# screen.net
KiCad netlist of a schematic drawn in Altium Designer
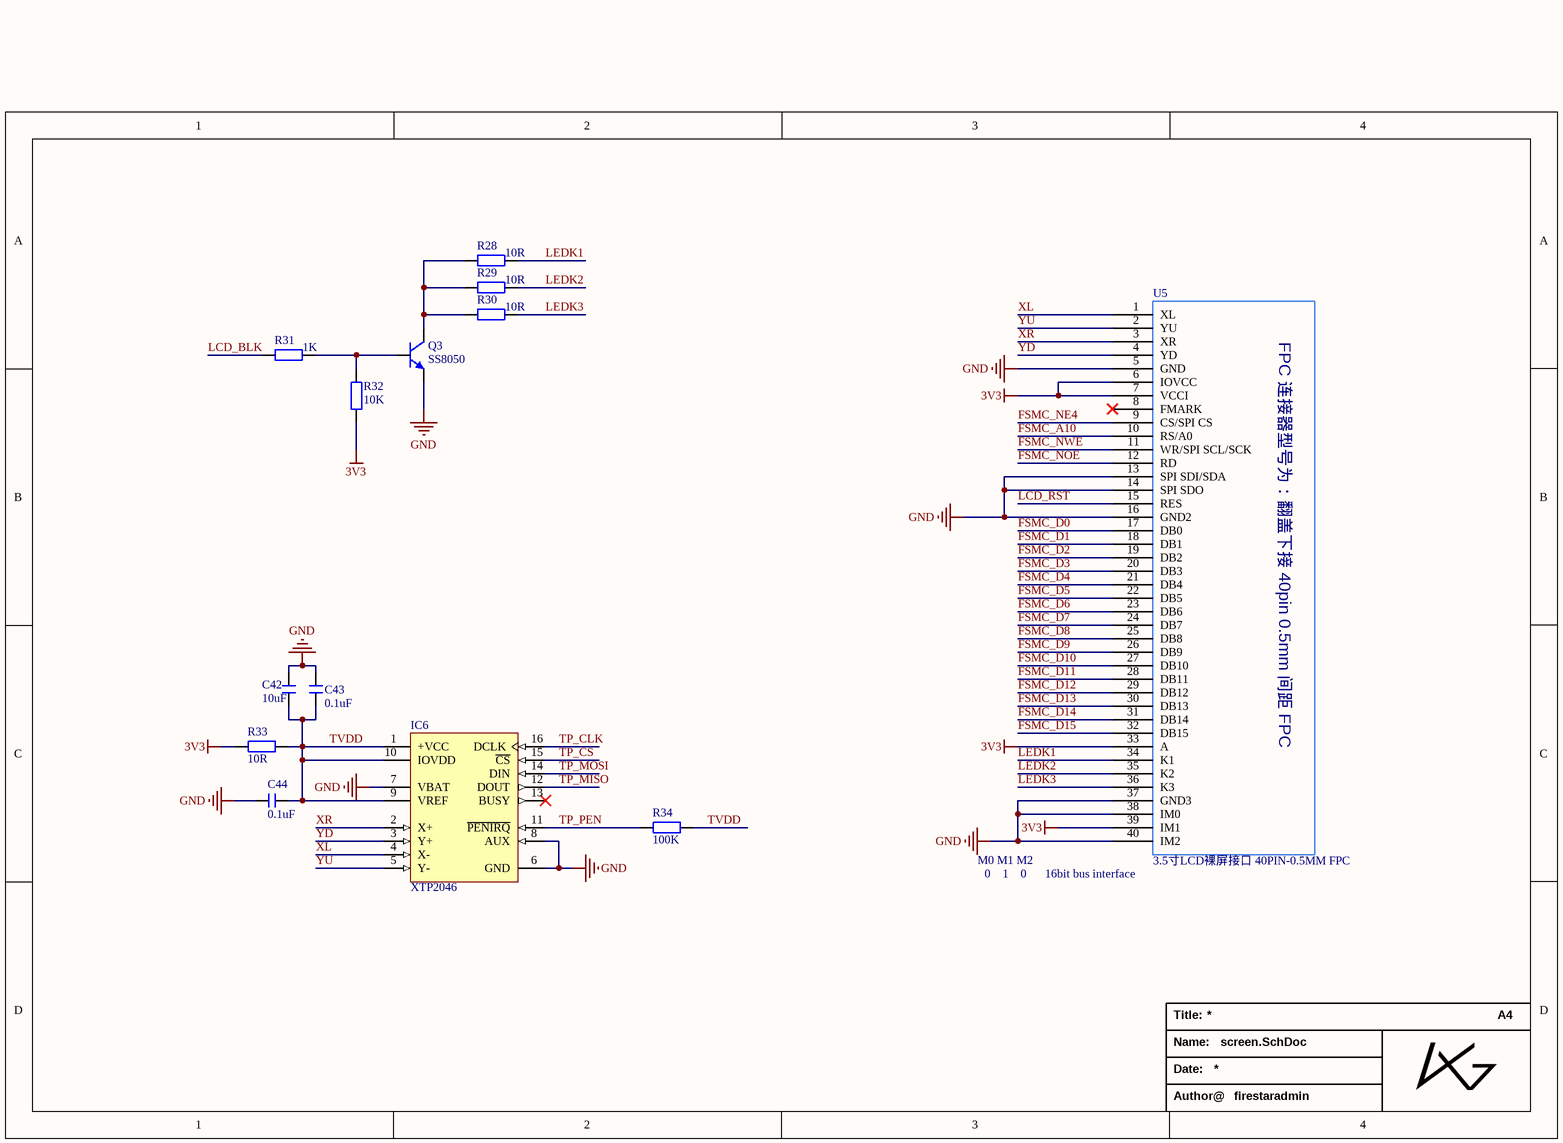
[diagram p0: screen.SchDoc]

(export (version "E")
  (design (tool "Eeschema 10.0.6"))
  (components
    (comp (ref "C42")
      (value "10uF")
      (footprint "C 0603_M")
      (description "无极性贴片电容")
      (fields (field (name "版权归属") "源创客"))
      (libsource (lib "3.1   - 电阻-电容-电感") (part "C"))
    )
    (comp (ref "C43")
      (value "0.1uF")
      (footprint "C 0603_M")
      (description "无极性贴片电容")
      (fields (field (name "版权归属") "源创客"))
      (libsource (lib "3.1   - 电阻-电容-电感") (part "C"))
    )
    (comp (ref "C44")
      (value "0.1uF")
      (footprint "C 0603_M")
      (description "无极性贴片电容")
      (fields (field (name "版权归属") "源创客"))
      (libsource (lib "3.1   - 电阻-电容-电感") (part "C"))
    )
    (comp (ref "IC6")
      (value "XTP2046")
      (footprint "TSSOP16_M")
      (description "显示屏触摸驱动芯片")
      (fields (field (name "版权归属") "源创客"))
      (libsource (lib "1.1   - IC芯片") (part "TSC2046IPW"))
    )
    (comp (ref "Q3")
      (value "SS8050")
      (footprint "SOT23-3M")
      (description "高频放大-NPN型")
      (fields (field (name "版权归属") "源创客"))
      (libsource (lib "6.2   - 三极管") (part "8050-SMD"))
    )
    (comp (ref "R28")
      (value "10R")
      (footprint "R 0603_M")
      (description "贴片电阻")
      (fields (field (name "版权归属") "源创客"))
      (libsource (lib "3.1   - 电阻-电容-电感") (part "R"))
    )
    (comp (ref "R29")
      (value "10R")
      (footprint "R 0603_M")
      (description "贴片电阻")
      (fields (field (name "版权归属") "源创客"))
      (libsource (lib "3.1   - 电阻-电容-电感") (part "R"))
    )
    (comp (ref "R30")
      (value "10R")
      (footprint "R 0603_M")
      (description "贴片电阻")
      (fields (field (name "版权归属") "源创客"))
      (libsource (lib "3.1   - 电阻-电容-电感") (part "R"))
    )
    (comp (ref "R31")
      (value "1K")
      (footprint "R 0603_M")
      (description "贴片电阻")
      (fields (field (name "版权归属") "源创客"))
      (libsource (lib "3.1   - 电阻-电容-电感") (part "R"))
    )
    (comp (ref "R32")
      (value "10K")
      (footprint "R 0603_M")
      (description "贴片电阻")
      (fields (field (name "版权归属") "源创客"))
      (libsource (lib "3.1   - 电阻-电容-电感") (part "R"))
    )
    (comp (ref "R33")
      (value "10R")
      (footprint "R 0603_M")
      (description "贴片电阻")
      (fields (field (name "版权归属") "源创客"))
      (libsource (lib "3.1   - 电阻-电容-电感") (part "R"))
    )
    (comp (ref "R34")
      (value "100K")
      (footprint "R 0603_M")
      (description "贴片电阻")
      (fields (field (name "版权归属") "源创客"))
      (libsource (lib "3.1   - 电阻-电容-电感") (part "R"))
    )
    (comp (ref "U5")
      (value "3.5寸LCD裸屏接口 40PIN-0.5MM FPC")
      (footprint "FPC0.5 2H-WS-40P")
      (description "3.5寸LCD屏幕 40PIN-0.5MM FPC 接口")
      (libsource (lib "MyLib") (part "3.5寸LCD裸屏接口 40PIN-0.5MM FPC"))
    )
  )
  (nets
    (net (code "1") (name "/FSMC_A10") (class "Default")
      (node (ref "U5") (pin "10") (pinfunction "RS/A0_10") (pintype "passive"))
    )
    (net (code "2") (name "/FSMC_D0") (class "Default")
      (node (ref "U5") (pin "17") (pinfunction "DB0_17") (pintype "passive"))
    )
    (net (code "3") (name "/FSMC_D1") (class "Default")
      (node (ref "U5") (pin "18") (pinfunction "DB1_18") (pintype "passive"))
    )
    (net (code "4") (name "/FSMC_D2") (class "Default")
      (node (ref "U5") (pin "19") (pinfunction "DB2_19") (pintype "passive"))
    )
    (net (code "5") (name "/FSMC_D3") (class "Default")
      (node (ref "U5") (pin "20") (pinfunction "DB3_20") (pintype "passive"))
    )
    (net (code "6") (name "/FSMC_D4") (class "Default")
      (node (ref "U5") (pin "21") (pinfunction "DB4_21") (pintype "passive"))
    )
    (net (code "7") (name "/FSMC_D5") (class "Default")
      (node (ref "U5") (pin "22") (pinfunction "DB5_22") (pintype "passive"))
    )
    (net (code "8") (name "/FSMC_D6") (class "Default")
      (node (ref "U5") (pin "23") (pinfunction "DB6_23") (pintype "passive"))
    )
    (net (code "9") (name "/FSMC_D7") (class "Default")
      (node (ref "U5") (pin "24") (pinfunction "DB7_24") (pintype "passive"))
    )
    (net (code "10") (name "/FSMC_D8") (class "Default")
      (node (ref "U5") (pin "25") (pinfunction "DB8_25") (pintype "passive"))
    )
    (net (code "11") (name "/FSMC_D9") (class "Default")
      (node (ref "U5") (pin "26") (pinfunction "DB9_26") (pintype "passive"))
    )
    (net (code "12") (name "/FSMC_D10") (class "Default")
      (node (ref "U5") (pin "27") (pinfunction "DB10_27") (pintype "passive"))
    )
    (net (code "13") (name "/FSMC_D11") (class "Default")
      (node (ref "U5") (pin "28") (pinfunction "DB11_28") (pintype "passive"))
    )
    (net (code "14") (name "/FSMC_D12") (class "Default")
      (node (ref "U5") (pin "29") (pinfunction "DB12_29") (pintype "passive"))
    )
    (net (code "15") (name "/FSMC_D13") (class "Default")
      (node (ref "U5") (pin "30") (pinfunction "DB13_30") (pintype "passive"))
    )
    (net (code "16") (name "/FSMC_D14") (class "Default")
      (node (ref "U5") (pin "31") (pinfunction "DB14_31") (pintype "passive"))
    )
    (net (code "17") (name "/FSMC_D15") (class "Default")
      (node (ref "U5") (pin "32") (pinfunction "DB15_32") (pintype "passive"))
    )
    (net (code "18") (name "/FSMC_NE4") (class "Default")
      (node (ref "U5") (pin "9") (pinfunction "CS/SPI_CS_9") (pintype "passive"))
    )
    (net (code "19") (name "/FSMC_NOE") (class "Default")
      (node (ref "U5") (pin "12") (pinfunction "RD_12") (pintype "passive"))
    )
    (net (code "20") (name "/FSMC_NWE") (class "Default")
      (node (ref "U5") (pin "11") (pinfunction "WR/SPI_SCL/SCK_11") (pintype "passive"))
    )
    (net (code "21") (name "/LCD_BLK") (class "Default")
      (node (ref "R31") (pin "1") (pinfunction "1_1") (pintype "passive"))
    )
    (net (code "22") (name "/LCD_RST") (class "Default")
      (node (ref "U5") (pin "15") (pinfunction "RES_15") (pintype "passive"))
    )
    (net (code "23") (name "/LEDK1") (class "Default")
      (node (ref "R28") (pin "2") (pinfunction "2_2") (pintype "passive"))
      (node (ref "U5") (pin "34") (pinfunction "K1_34") (pintype "passive"))
    )
    (net (code "24") (name "/LEDK2") (class "Default")
      (node (ref "R29") (pin "2") (pinfunction "2_2") (pintype "passive"))
      (node (ref "U5") (pin "35") (pinfunction "K2_35") (pintype "passive"))
    )
    (net (code "25") (name "/LEDK3") (class "Default")
      (node (ref "R30") (pin "2") (pinfunction "2_2") (pintype "passive"))
      (node (ref "U5") (pin "36") (pinfunction "K3_36") (pintype "passive"))
    )
    (net (code "26") (name "/TP_CLK") (class "Default")
      (node (ref "IC6") (pin "16") (pinfunction "DCLK_16") (pintype "input"))
    )
    (net (code "27") (name "/TP_CS") (class "Default")
      (node (ref "IC6") (pin "15") (pinfunction "~{CS}_15") (pintype "input"))
    )
    (net (code "28") (name "/TP_MISO") (class "Default")
      (node (ref "IC6") (pin "12") (pinfunction "DOUT_12") (pintype "output"))
    )
    (net (code "29") (name "/TP_MOSI") (class "Default")
      (node (ref "IC6") (pin "14") (pinfunction "DIN_14") (pintype "input"))
    )
    (net (code "30") (name "/TP_PEN") (class "Default")
      (node (ref "IC6") (pin "11") (pinfunction "~{PENIRQ}_11") (pintype "input"))
      (node (ref "R34") (pin "1") (pinfunction "1_1") (pintype "passive"))
    )
    (net (code "31") (name "/TVDD") (class "Default")
      (node (ref "C42") (pin "2") (pinfunction "2_2") (pintype "passive"))
      (node (ref "C43") (pin "2") (pinfunction "2_2") (pintype "passive"))
      (node (ref "C44") (pin "1") (pinfunction "1_1") (pintype "passive"))
      (node (ref "IC6") (pin "1") (pinfunction "+VCC_1") (pintype "power_in"))
      (node (ref "IC6") (pin "10") (pinfunction "IOVDD_10") (pintype "power_in"))
      (node (ref "IC6") (pin "9") (pinfunction "VREF_9") (pintype "power_in"))
      (node (ref "R33") (pin "2") (pinfunction "2_2") (pintype "passive"))
      (node (ref "R34") (pin "2") (pinfunction "2_2") (pintype "passive"))
    )
    (net (code "32") (name "/XL") (class "Default")
      (node (ref "IC6") (pin "4") (pinfunction "X-_4") (pintype "input"))
      (node (ref "U5") (pin "1") (pinfunction "XL_1") (pintype "passive"))
    )
    (net (code "33") (name "/XR") (class "Default")
      (node (ref "IC6") (pin "2") (pinfunction "X+_2") (pintype "input"))
      (node (ref "U5") (pin "3") (pinfunction "XR_3") (pintype "passive"))
    )
    (net (code "34") (name "/YD") (class "Default")
      (node (ref "IC6") (pin "3") (pinfunction "Y+_3") (pintype "input"))
      (node (ref "U5") (pin "4") (pinfunction "YD_4") (pintype "passive"))
    )
    (net (code "35") (name "/YU") (class "Default")
      (node (ref "IC6") (pin "5") (pinfunction "Y-_5") (pintype "input"))
      (node (ref "U5") (pin "2") (pinfunction "YU_2") (pintype "passive"))
    )
    (net (code "36") (name "3V3") (class "Default")
      (node (ref "R32") (pin "1") (pinfunction "1_1") (pintype "passive"))
      (node (ref "R33") (pin "1") (pinfunction "1_1") (pintype "passive"))
      (node (ref "U5") (pin "33") (pinfunction "A_33") (pintype "passive"))
      (node (ref "U5") (pin "39") (pinfunction "IM1_39") (pintype "passive"))
      (node (ref "U5") (pin "6") (pinfunction "IOVCC_6") (pintype "passive"))
      (node (ref "U5") (pin "7") (pinfunction "VCCI_7") (pintype "passive"))
    )
    (net (code "37") (name "GND") (class "Default")
      (node (ref "C42") (pin "1") (pinfunction "1_1") (pintype "passive"))
      (node (ref "C43") (pin "1") (pinfunction "1_1") (pintype "passive"))
      (node (ref "C44") (pin "2") (pinfunction "2_2") (pintype "passive"))
      (node (ref "IC6") (pin "6") (pinfunction "GND_6") (pintype "power_in"))
      (node (ref "IC6") (pin "7") (pinfunction "VBAT_7") (pintype "power_in"))
      (node (ref "IC6") (pin "8") (pinfunction "AUX_8") (pintype "input"))
      (node (ref "Q3") (pin "2") (pinfunction "E_2") (pintype "passive"))
      (node (ref "U5") (pin "13") (pinfunction "SPI_SDI/SDA_13") (pintype "passive"))
      (node (ref "U5") (pin "14") (pinfunction "SPI_SDO_14") (pintype "passive"))
      (node (ref "U5") (pin "16") (pinfunction "GND2_16") (pintype "passive"))
      (node (ref "U5") (pin "37") (pinfunction "GND3_37") (pintype "passive"))
      (node (ref "U5") (pin "38") (pinfunction "IM0_38") (pintype "passive"))
      (node (ref "U5") (pin "40") (pinfunction "IM2_40") (pintype "passive"))
      (node (ref "U5") (pin "5") (pinfunction "GND_5") (pintype "passive"))
    )
    (net (code "38") (name "Net-(Q3-B)") (class "Default")
      (node (ref "Q3") (pin "1") (pinfunction "B_1") (pintype "passive"))
      (node (ref "R31") (pin "2") (pinfunction "2_2") (pintype "passive"))
      (node (ref "R32") (pin "2") (pinfunction "2_2") (pintype "passive"))
    )
    (net (code "39") (name "Net-(Q3-C)") (class "Default")
      (node (ref "Q3") (pin "3") (pinfunction "C_3") (pintype "passive"))
      (node (ref "R28") (pin "1") (pinfunction "1_1") (pintype "passive"))
      (node (ref "R29") (pin "1") (pinfunction "1_1") (pintype "passive"))
      (node (ref "R30") (pin "1") (pinfunction "1_1") (pintype "passive"))
    )
    (net (code "40") (name "unconnected-(IC6-BUSY-Pad13)") (class "Default")
      (node (ref "IC6") (pin "13") (pinfunction "BUSY_13") (pintype "output+no_connect"))
    )
    (net (code "41") (name "unconnected-(U5-FMARK-Pad8)") (class "Default")
      (node (ref "U5") (pin "8") (pinfunction "FMARK_8") (pintype "passive+no_connect"))
    )
  )
)
